# piezo-preamp-tickler_V2-RevB_LOCAL_7081.net
KiCad netlist of a schematic drawn in EAGLE
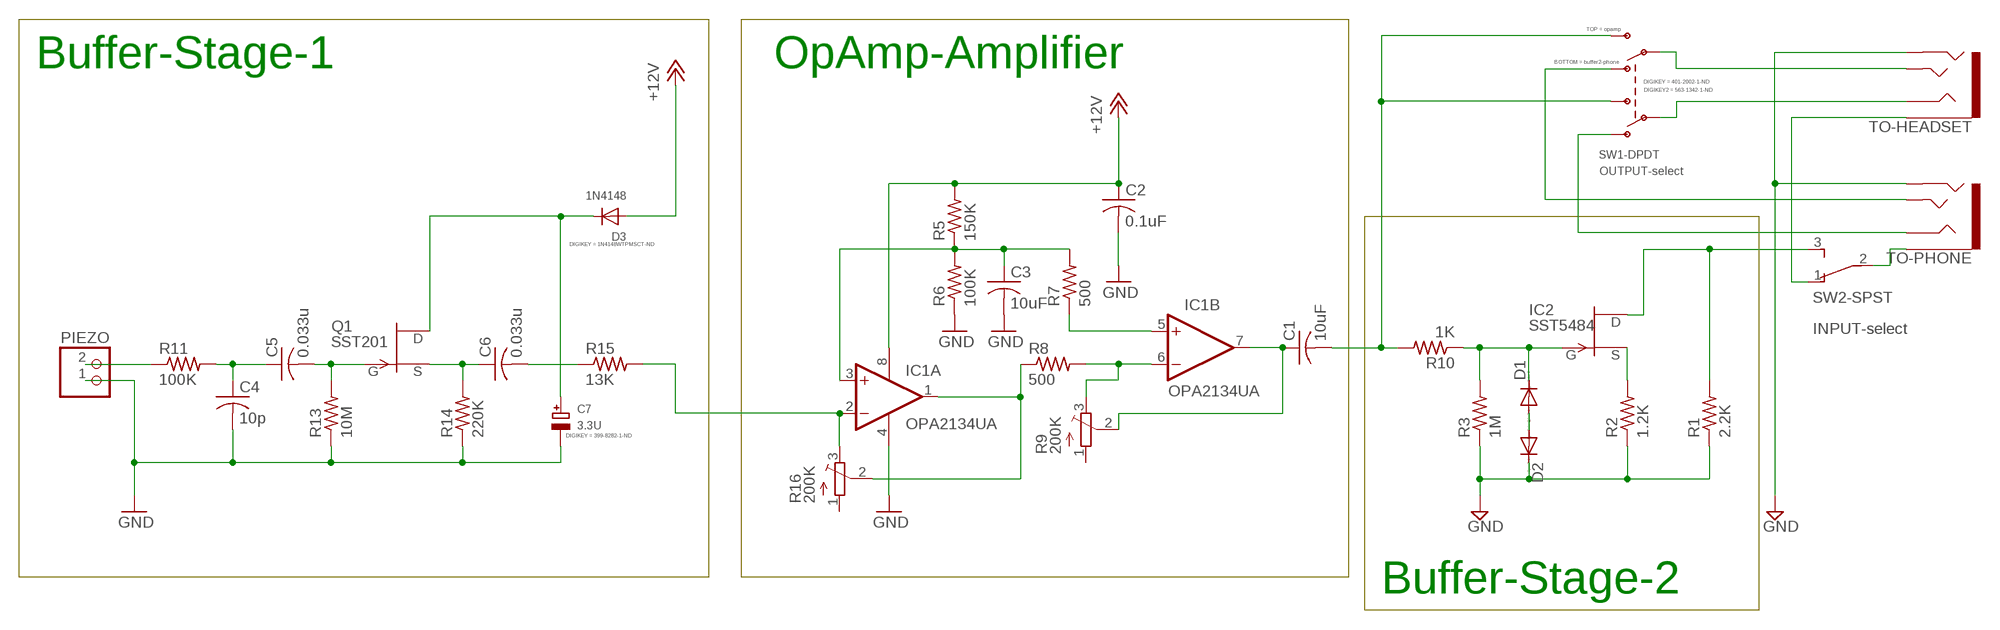
[diagram p0: schematic, sheet 1]
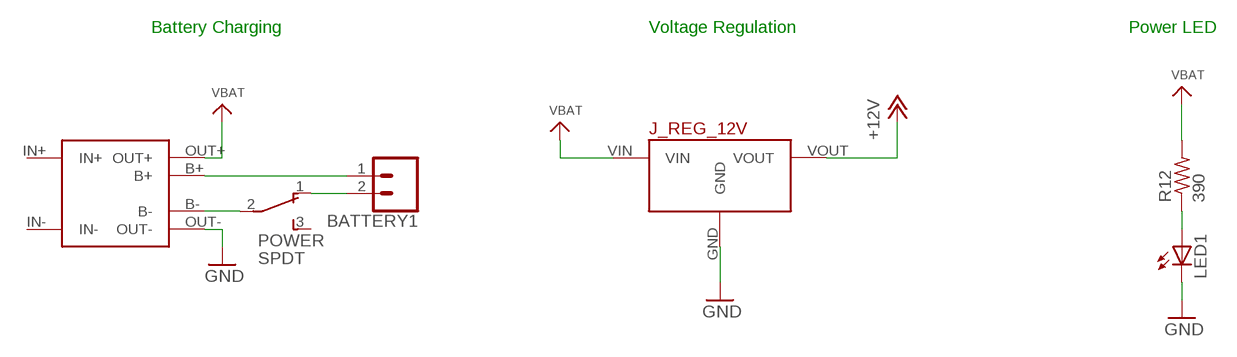
[diagram p1: schematic, sheet 2]

(export (version "E")
  (design (tool "Eeschema 10.0.6"))
  (components
    (comp (ref "BATTERY1")
      (value "CONN_02LOCK")
      (footprint "eagle-import:1X02_LOCK")
      (libsource (lib "eagle-import") (part "CONN_02LOCK"))
    )
    (comp (ref "J_REG_12V")
      (value "POLOLU_VOLTAGE_REGULATORS_3PIN")
      (footprint "eagle-import:POLOLU_5V-12V_STEPUP_U3V12F5-U3V12F12")
      (libsource (lib "eagle-import") (part "POLOLU_VOLTAGE_REGULATORS_3PIN"))
    )
    (comp (ref "LED1")
      (value "LED3MM")
      (footprint "eagle-import:LED3MM")
      (libsource (lib "eagle-import") (part "LED3MM"))
    )
    (comp (ref "POWER")
      (value "SPDT")
      (footprint "eagle-import:SWITCH_SPDT-TE-CONNECT")
      (libsource (lib "eagle-import") (part "SWITCH_SPDTTE-CONNECT"))
    )
    (comp (ref "R12")
      (value "390")
      (footprint "eagle-import:R0805")
      (libsource (lib "eagle-import") (part "R-US_R0805"))
    )
    (comp (ref "USB-LIPO-CHARGER")
      (value "TP4056-MODULE")
      (footprint "eagle-import:TP4056-LITHIUM-PROTECTED-MODULE")
      (libsource (lib "eagle-import") (part "TP4056-MODULE"))
    )
    (comp (ref "C1")
      (value "10uF")
      (footprint "eagle-import:C0805K")
      (libsource (lib "eagle-import") (part "C-USC0805K"))
    )
    (comp (ref "C2")
      (value "0.1uF")
      (footprint "eagle-import:C0805K")
      (libsource (lib "eagle-import") (part "C-USC0805K"))
    )
    (comp (ref "C3")
      (value "10uF")
      (footprint "eagle-import:C0805K")
      (libsource (lib "eagle-import") (part "C-USC0805K"))
    )
    (comp (ref "C4")
      (value "10p")
      (footprint "eagle-import:C0805K")
      (libsource (lib "eagle-import") (part "C-USC0805K"))
    )
    (comp (ref "C5")
      (value "0.033u")
      (footprint "eagle-import:C0805K")
      (libsource (lib "eagle-import") (part "C-USC0805K"))
    )
    (comp (ref "C6")
      (value "0.033u")
      (footprint "eagle-import:C0805K")
      (libsource (lib "eagle-import") (part "C-USC0805K"))
    )
    (comp (ref "C7")
      (value "3.3U")
      (footprint "eagle-import:EIA3216-18_A-R")
      (fields (field (name "DIGIKEY") "399-8282-1-ND"))
      (libsource (lib "eagle-import") (part "CAP_TANTALUMA/3216_REFLOW"))
    )
    (comp (ref "D1")
      (value "DIODE-SOD123")
      (footprint "eagle-import:SOD123")
      (libsource (lib "eagle-import") (part "DIODE-SOD123"))
    )
    (comp (ref "D2")
      (value "DIODE-SOD123")
      (footprint "eagle-import:SOD123")
      (libsource (lib "eagle-import") (part "DIODE-SOD123"))
    )
    (comp (ref "D3")
      (value "1N4148")
      (footprint "eagle-import:SOD-123")
      (fields (field (name "DIGIKEY") "1N4148WTPMSCT-ND"))
      (libsource (lib "eagle-import") (part "DIODESOD-123"))
    )
    (comp (ref "IC1")
      (value "OPA2134UA")
      (footprint "eagle-import:SO08")
      (libsource (lib "eagle-import") (part "OPA2UA134"))
    )
    (comp (ref "IC2")
      (value "SST5484")
      (footprint "eagle-import:SOT23")
      (libsource (lib "eagle-import") (part "?548SST4"))
    )
    (comp (ref "PIEZO")
      (value "JST_2PIN-THM")
      (footprint "eagle-import:JST-PH-2-THM")
      (libsource (lib "eagle-import") (part "JST_2PIN-THM"))
    )
    (comp (ref "Q1")
      (value "SST201")
      (footprint "eagle-import:SOT23")
      (libsource (lib "eagle-import") (part "?20SST1"))
    )
    (comp (ref "R1")
      (value "2.2K")
      (footprint "eagle-import:R0603")
      (libsource (lib "eagle-import") (part "R-US_R0603"))
    )
    (comp (ref "R2")
      (value "1.2K")
      (footprint "eagle-import:R0603")
      (libsource (lib "eagle-import") (part "R-US_R0603"))
    )
    (comp (ref "R3")
      (value "1M")
      (footprint "eagle-import:R0603")
      (libsource (lib "eagle-import") (part "R-US_R0603"))
    )
    (comp (ref "R5")
      (value "150K")
      (footprint "eagle-import:R0603")
      (libsource (lib "eagle-import") (part "R-US_R0603"))
    )
    (comp (ref "R6")
      (value "100K")
      (footprint "eagle-import:R0603")
      (libsource (lib "eagle-import") (part "R-US_R0603"))
    )
    (comp (ref "R7")
      (value "500")
      (footprint "eagle-import:R0603")
      (libsource (lib "eagle-import") (part "R-US_R0603"))
    )
    (comp (ref "R8")
      (value "500")
      (footprint "eagle-import:R0603")
      (libsource (lib "eagle-import") (part "R-US_R0603"))
    )
    (comp (ref "R9")
      (value "200K")
      (footprint "eagle-import:TC33X")
      (libsource (lib "eagle-import") (part "TRIMPOTTC33X"))
    )
    (comp (ref "R10")
      (value "1K")
      (footprint "eagle-import:R0603")
      (libsource (lib "eagle-import") (part "R-US_R0603"))
    )
    (comp (ref "R11")
      (value "100K")
      (footprint "eagle-import:R0603")
      (libsource (lib "eagle-import") (part "R-US_R0603"))
    )
    (comp (ref "R13")
      (value "10M")
      (footprint "eagle-import:R0603")
      (libsource (lib "eagle-import") (part "R-US_R0603"))
    )
    (comp (ref "R14")
      (value "220K")
      (footprint "eagle-import:R0603")
      (libsource (lib "eagle-import") (part "R-US_R0603"))
    )
    (comp (ref "R15")
      (value "13K")
      (footprint "eagle-import:R0603")
      (libsource (lib "eagle-import") (part "R-US_R0603"))
    )
    (comp (ref "R16")
      (value "200K")
      (footprint "eagle-import:TC33X")
      (libsource (lib "eagle-import") (part "TRIMPOTTC33X"))
    )
    (comp (ref "SW1-DPDT")
      (value "OUTPUT-select")
      (footprint "eagle-import:DPDT_SMT_JS202011SCQN")
      (fields
        (field (name "BOTTOM") "buffer2-phone")
        (field (name "DIGIKEY") "401-2002-1-ND")
        (field (name "DIGIKEY2") "563-1342-1-ND")
        (field (name "TOP") "opamp")
      )
      (libsource (lib "eagle-import") (part "SWITCH_DPDT"))
    )
    (comp (ref "SW2-SPST")
      (value "INPUT-select")
      (footprint "eagle-import:SWITCH_SPDT-TE-CONNECT")
      (libsource (lib "eagle-import") (part "SWITCH_SPDTTE-CONNECT"))
    )
    (comp (ref "TO-HEADSET")
      (value "AUDIO-JACK3LGPADS")
      (footprint "eagle-import:AUDIO-JACK-TRRS-SMD")
      (libsource (lib "eagle-import") (part "AUDIO-JACK3LGPADS"))
    )
    (comp (ref "TO-PHONE")
      (value "AUDIO-JACK3LGPADS")
      (footprint "eagle-import:AUDIO-JACK-TRRS-SMD")
      (libsource (lib "eagle-import") (part "AUDIO-JACK3LGPADS"))
    )
  )
  (nets
    (net (code "1") (name "+12V") (class "Default")
      (node (ref "C2") (pin "1") (pinfunction "1_1") (pintype "passive"))
      (node (ref "D3") (pin "A") (pinfunction "A_A") (pintype "passive"))
      (node (ref "IC1") (pin "8") (pinfunction "V+_8") (pintype "power_in"))
      (node (ref "J_REG_12V") (pin "VOUT") (pinfunction "VOUT_VOUT") (pintype "bidirectional"))
      (node (ref "R5") (pin "2") (pinfunction "2_2") (pintype "passive"))
    )
    (net (code "2") (name "GND") (class "Default")
      (node (ref "C2") (pin "2") (pinfunction "2_2") (pintype "passive"))
      (node (ref "C3") (pin "2") (pinfunction "2_2") (pintype "passive"))
      (node (ref "C4") (pin "2") (pinfunction "2_2") (pintype "passive"))
      (node (ref "C7") (pin "-") (pinfunction "-_-") (pintype "passive"))
      (node (ref "D2") (pin "C") (pinfunction "C_C") (pintype "passive"))
      (node (ref "IC1") (pin "4") (pinfunction "V-_4") (pintype "power_in"))
      (node (ref "J_REG_12V") (pin "GND") (pinfunction "GND_GND") (pintype "bidirectional"))
      (node (ref "LED1") (pin "K") (pinfunction "C_K") (pintype "passive"))
      (node (ref "PIEZO") (pin "1") (pinfunction "2_1") (pintype "passive"))
      (node (ref "R1") (pin "1") (pinfunction "1_1") (pintype "passive"))
      (node (ref "R13") (pin "1") (pinfunction "1_1") (pintype "passive"))
      (node (ref "R14") (pin "1") (pinfunction "1_1") (pintype "passive"))
      (node (ref "R2") (pin "1") (pinfunction "1_1") (pintype "passive"))
      (node (ref "R3") (pin "1") (pinfunction "1_1") (pintype "passive"))
      (node (ref "R6") (pin "1") (pinfunction "1_1") (pintype "passive"))
      (node (ref "TO-HEADSET") (pin "RING2") (pinfunction "RING2_RING2") (pintype "bidirectional"))
      (node (ref "TO-PHONE") (pin "RING2") (pinfunction "RING2_RING2") (pintype "bidirectional"))
      (node (ref "USB-LIPO-CHARGER") (pin "OUT-") (pinfunction "OUT-_OUT-") (pintype "power_in"))
    )
    (net (code "3") (name "IN+") (class "Default")
      (node (ref "USB-LIPO-CHARGER") (pin "IN+") (pinfunction "IN+_IN+") (pintype "power_in"))
    )
    (net (code "4") (name "IN-") (class "Default")
      (node (ref "USB-LIPO-CHARGER") (pin "IN-") (pinfunction "IN-_IN-") (pintype "power_in"))
    )
    (net (code "5") (name "Net-(BATTERY1-Pad1)") (class "Default")
      (node (ref "BATTERY1") (pin "1") (pinfunction "1_1") (pintype "passive"))
      (node (ref "USB-LIPO-CHARGER") (pin "B+") (pinfunction "B+_B+") (pintype "power_in"))
    )
    (net (code "6") (name "Net-(BATTERY1-Pad2)") (class "Default")
      (node (ref "BATTERY1") (pin "2") (pinfunction "2_2") (pintype "passive"))
      (node (ref "POWER") (pin "1") (pinfunction "1_1") (pintype "passive"))
    )
    (net (code "7") (name "Net-(C4-Pad1)") (class "Default")
      (node (ref "C4") (pin "1") (pinfunction "1_1") (pintype "passive"))
      (node (ref "C5") (pin "1") (pinfunction "1_1") (pintype "passive"))
      (node (ref "R11") (pin "2") (pinfunction "2_2") (pintype "passive"))
    )
    (net (code "8") (name "Net-(C6-Pad2)") (class "Default")
      (node (ref "C6") (pin "2") (pinfunction "2_2") (pintype "passive"))
      (node (ref "R15") (pin "1") (pinfunction "1_1") (pintype "passive"))
    )
    (net (code "9") (name "Net-(D1-PadA)") (class "Default")
      (node (ref "D1") (pin "A") (pinfunction "A_A") (pintype "passive"))
      (node (ref "D2") (pin "A") (pinfunction "A_A") (pintype "passive"))
    )
    (net (code "10") (name "Net-(IC1A-+IN)") (class "Default")
      (node (ref "C3") (pin "1") (pinfunction "1_1") (pintype "passive"))
      (node (ref "IC1") (pin "3") (pinfunction "+IN_3") (pintype "input"))
      (node (ref "R5") (pin "1") (pinfunction "1_1") (pintype "passive"))
      (node (ref "R6") (pin "2") (pinfunction "2_2") (pintype "passive"))
      (node (ref "R7") (pin "2") (pinfunction "2_2") (pintype "passive"))
    )
    (net (code "11") (name "Net-(IC1A--IN)") (class "Default")
      (node (ref "IC1") (pin "2") (pinfunction "-IN_2") (pintype "input"))
      (node (ref "R15") (pin "2") (pinfunction "2_2") (pintype "passive"))
      (node (ref "R16") (pin "3") (pinfunction "E_3") (pintype "passive"))
    )
    (net (code "12") (name "Net-(IC1A-OUT)") (class "Default")
      (node (ref "IC1") (pin "1") (pinfunction "OUT_1") (pintype "output"))
      (node (ref "R16") (pin "2") (pinfunction "S_2") (pintype "passive"))
      (node (ref "R8") (pin "1") (pinfunction "1_1") (pintype "passive"))
    )
    (net (code "13") (name "Net-(IC1B-+IN)") (class "Default")
      (node (ref "IC1") (pin "5") (pinfunction "+IN_5") (pintype "input"))
      (node (ref "R7") (pin "1") (pinfunction "1_1") (pintype "passive"))
    )
    (net (code "14") (name "Net-(IC1B--IN)") (class "Default")
      (node (ref "IC1") (pin "6") (pinfunction "-IN_6") (pintype "input"))
      (node (ref "R8") (pin "2") (pinfunction "2_2") (pintype "passive"))
      (node (ref "R9") (pin "3") (pinfunction "E_3") (pintype "passive"))
    )
    (net (code "15") (name "Net-(IC1B-OUT)") (class "Default")
      (node (ref "C1") (pin "1") (pinfunction "1_1") (pintype "passive"))
      (node (ref "IC1") (pin "7") (pinfunction "OUT_7") (pintype "output"))
      (node (ref "R9") (pin "2") (pinfunction "S_2") (pintype "passive"))
    )
    (net (code "16") (name "Net-(IC2-D)") (class "Default")
      (node (ref "IC2") (pin "1") (pinfunction "D_1") (pintype "passive"))
      (node (ref "R1") (pin "2") (pinfunction "2_2") (pintype "passive"))
      (node (ref "SW2-SPST") (pin "3") (pinfunction "3_3") (pintype "passive"))
    )
    (net (code "17") (name "Net-(IC2-G)") (class "Default")
      (node (ref "D1") (pin "C") (pinfunction "C_C") (pintype "passive"))
      (node (ref "IC2") (pin "3") (pinfunction "G_3") (pintype "passive"))
      (node (ref "R10") (pin "1") (pinfunction "1_1") (pintype "passive"))
      (node (ref "R3") (pin "2") (pinfunction "2_2") (pintype "passive"))
    )
    (net (code "18") (name "Net-(IC2-S)") (class "Default")
      (node (ref "IC2") (pin "2") (pinfunction "S_2") (pintype "passive"))
      (node (ref "R2") (pin "2") (pinfunction "2_2") (pintype "passive"))
    )
    (net (code "19") (name "Net-(LED1-PadA)") (class "Default")
      (node (ref "LED1") (pin "A") (pinfunction "A_A") (pintype "passive"))
      (node (ref "R12") (pin "1") (pinfunction "1_1") (pintype "passive"))
    )
    (net (code "20") (name "Net-(PIEZO-1)") (class "Default")
      (node (ref "PIEZO") (pin "2") (pinfunction "1_2") (pintype "passive"))
      (node (ref "R11") (pin "1") (pinfunction "1_1") (pintype "passive"))
    )
    (net (code "21") (name "Net-(POWER-Pad2)") (class "Default")
      (node (ref "POWER") (pin "2") (pinfunction "2_2") (pintype "passive"))
      (node (ref "USB-LIPO-CHARGER") (pin "B-") (pinfunction "B-_B-") (pintype "power_in"))
    )
    (net (code "22") (name "Net-(Q1-D)") (class "Default")
      (node (ref "C7") (pin "+") (pinfunction "+_+") (pintype "passive"))
      (node (ref "D3") (pin "C") (pinfunction "C_C") (pintype "passive"))
      (node (ref "Q1") (pin "1") (pinfunction "D_1") (pintype "passive"))
    )
    (net (code "23") (name "Net-(Q1-G)") (class "Default")
      (node (ref "C5") (pin "2") (pinfunction "2_2") (pintype "passive"))
      (node (ref "Q1") (pin "3") (pinfunction "G_3") (pintype "passive"))
      (node (ref "R13") (pin "2") (pinfunction "2_2") (pintype "passive"))
    )
    (net (code "24") (name "Net-(Q1-S)") (class "Default")
      (node (ref "C6") (pin "1") (pinfunction "1_1") (pintype "passive"))
      (node (ref "Q1") (pin "2") (pinfunction "S_2") (pintype "passive"))
      (node (ref "R14") (pin "2") (pinfunction "2_2") (pintype "passive"))
    )
    (net (code "25") (name "Net-(SW1-DPDT-O1)") (class "Default")
      (node (ref "SW1-DPDT") (pin "P$1") (pinfunction "O1_P$1") (pintype "passive"))
      (node (ref "TO-PHONE") (pin "RING1") (pinfunction "RING1_RING1") (pintype "bidirectional"))
    )
    (net (code "26") (name "Net-(SW1-DPDT-O2)") (class "Default")
      (node (ref "SW1-DPDT") (pin "P$6") (pinfunction "O2_P$6") (pintype "passive"))
      (node (ref "TO-PHONE") (pin "TIP") (pinfunction "TIP_TIP") (pintype "bidirectional"))
    )
    (net (code "27") (name "Net-(SW1-DPDT-P1)") (class "Default")
      (node (ref "SW1-DPDT") (pin "P$2") (pinfunction "P1_P$2") (pintype "passive"))
      (node (ref "TO-HEADSET") (pin "RING1") (pinfunction "RING1_RING1") (pintype "bidirectional"))
    )
    (net (code "28") (name "Net-(SW1-DPDT-P2)") (class "Default")
      (node (ref "SW1-DPDT") (pin "P$5") (pinfunction "P2_P$5") (pintype "passive"))
      (node (ref "TO-HEADSET") (pin "TIP") (pinfunction "TIP_TIP") (pintype "bidirectional"))
    )
    (net (code "29") (name "Net-(SW1-DPDT-S1)") (class "Default")
      (node (ref "C1") (pin "2") (pinfunction "2_2") (pintype "passive"))
      (node (ref "R10") (pin "2") (pinfunction "2_2") (pintype "passive"))
      (node (ref "SW1-DPDT") (pin "P$3") (pinfunction "S1_P$3") (pintype "passive"))
      (node (ref "SW1-DPDT") (pin "P$4") (pinfunction "S2_P$4") (pintype "passive"))
    )
    (net (code "30") (name "Net-(SW2-SPST-Pad1)") (class "Default")
      (node (ref "SW2-SPST") (pin "1") (pinfunction "1_1") (pintype "passive"))
      (node (ref "TO-HEADSET") (pin "EARTH") (pinfunction "EARTH_EARTH") (pintype "bidirectional"))
    )
    (net (code "31") (name "Net-(SW2-SPST-Pad2)") (class "Default")
      (node (ref "SW2-SPST") (pin "2") (pinfunction "2_2") (pintype "passive"))
      (node (ref "TO-PHONE") (pin "EARTH") (pinfunction "EARTH_EARTH") (pintype "bidirectional"))
    )
    (net (code "32") (name "VBAT") (class "Default")
      (node (ref "J_REG_12V") (pin "VIN") (pinfunction "VIN_VIN") (pintype "bidirectional"))
      (node (ref "R12") (pin "2") (pinfunction "2_2") (pintype "passive"))
      (node (ref "USB-LIPO-CHARGER") (pin "OUT+") (pinfunction "OUT+_OUT+") (pintype "power_in"))
    )
    (net (code "33") (name "unconnected-(POWER-Pad3)") (class "Default")
      (node (ref "POWER") (pin "3") (pinfunction "3_3") (pintype "passive"))
    )
    (net (code "34") (name "unconnected-(R9-A-Pad1)") (class "Default")
      (node (ref "R9") (pin "1") (pinfunction "A_1") (pintype "passive"))
    )
    (net (code "35") (name "unconnected-(R16-A-Pad1)") (class "Default")
      (node (ref "R16") (pin "1") (pinfunction "A_1") (pintype "passive"))
    )
  )
)
